# Power.net
KiCad netlist of a schematic drawn in Altium Designer
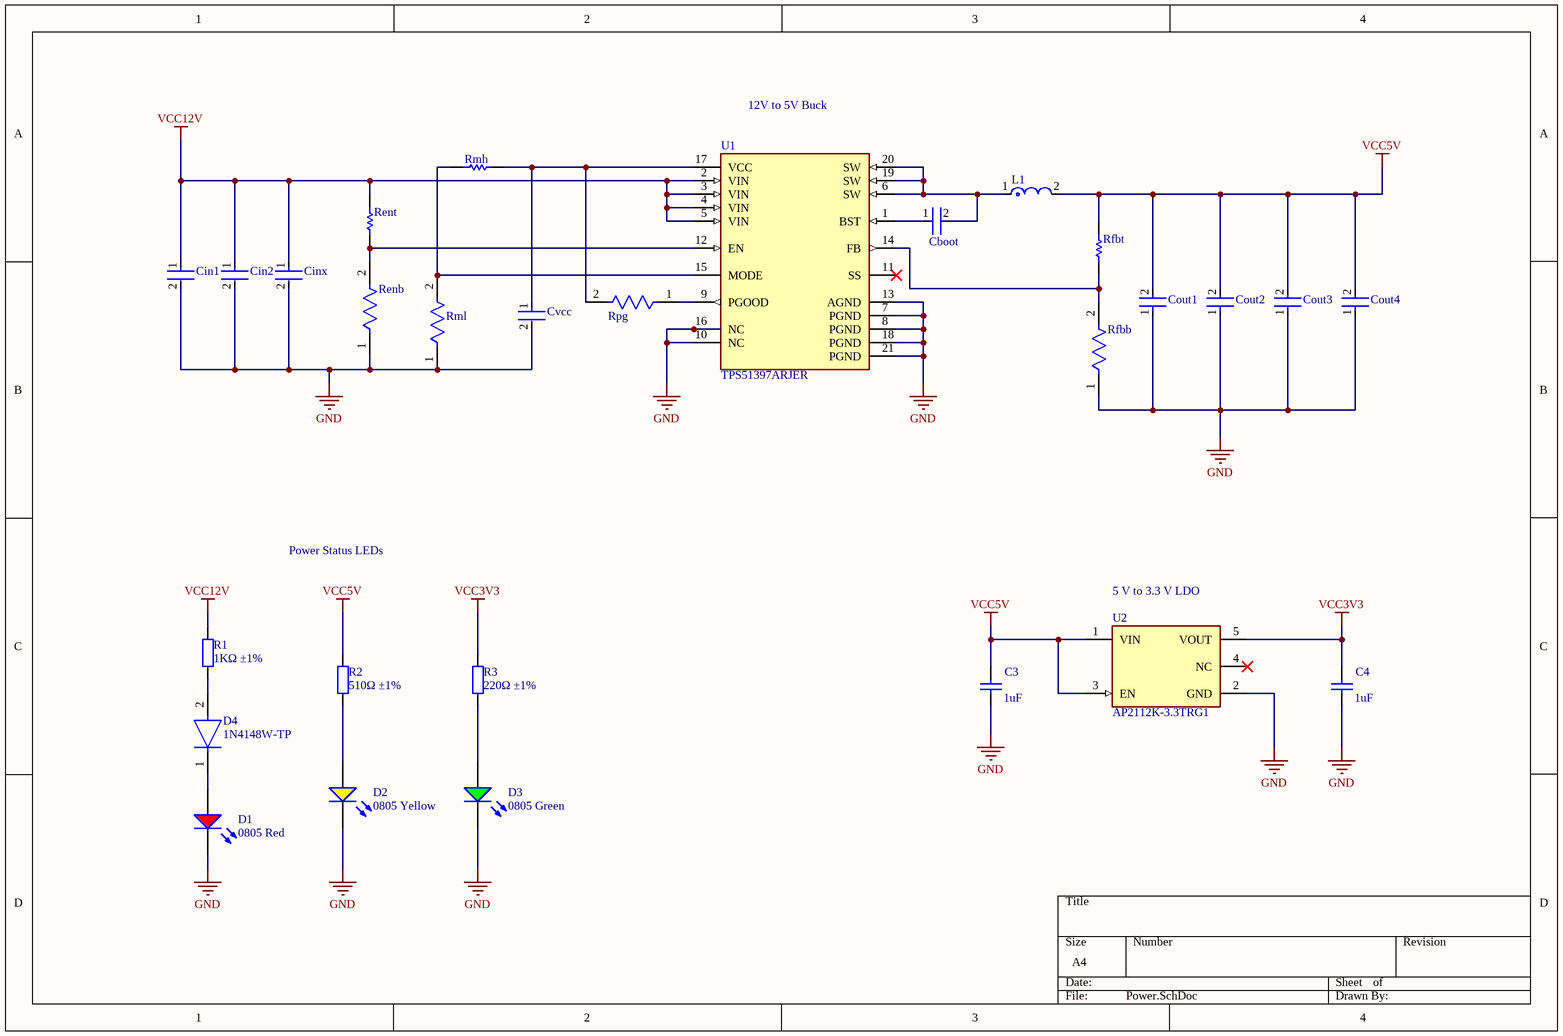
[diagram p0: Power.SchDoc]

(export (version "E")
  (design (tool "Eeschema 10.0.6"))
  (components
    (comp (ref "C3")
      (value "1uF")
      (footprint "0805_C")
      (description "Chip capacitors")
      (fields
        (field (name "MANUFACTURER") "Samsung Electro-Mechanics")
        (field (name "PARTNUMBER") "CL21B105KBFNNNE")
      )
      (libsource (lib "Cap") (part "0805 1uF (105) 10% 50V"))
    )
    (comp (ref "C4")
      (value "1uF")
      (footprint "0805_C")
      (description "Chip capacitors")
      (fields
        (field (name "MANUFACTURER") "Samsung Electro-Mechanics")
        (field (name "PARTNUMBER") "CL21B105KBFNNNE")
      )
      (libsource (lib "Cap") (part "0805 1uF (105) 10% 50V"))
    )
    (comp (ref "Cboot")
      (value "GRM155R71C104KA88D")
      (footprint "FP-GRM15-MFG")
      (description "CAP CER 0.1UF 16V X7R 0402")
      (fields
        (field (name "TOLERANCE") "10%")
        (field (name "OCTOPART") "https://octopart.com/grm155r71c104ka88d-murata-196880")
      )
      (libsource (lib "Altium Content Vault") (part "236180d848d6139a670b325ea6854c9"))
    )
    (comp (ref "Cin1")
      (value "C2012X5R1V226M125AC")
      (footprint "FP-C2012-125-0_2-MFG")
      (description "Multilayer Ceramic Capacitors 22μF ±20% 35V X5R SMD 0805")
      (fields (field (name "TOLERANCE") "20%"))
      (libsource (lib "Altium Content Vault") (part "b4654b650e69147ec39a6b967a45e02"))
    )
    (comp (ref "Cin2")
      (value "C2012X5R1V226M125AC")
      (footprint "FP-C2012-125-0_2-MFG")
      (description "Multilayer Ceramic Capacitors 22μF ±20% 35V X5R SMD 0805")
      (fields (field (name "TOLERANCE") "20%"))
      (libsource (lib "Altium Content Vault") (part "b4654b650e69147ec39a6b967a45e02"))
    )
    (comp (ref "Cinx")
      (value "CGA3E2X7R1H104K080AA")
      (footprint "FP-CGA3E-0_3-0_1-IPC_A")
      (description "Cap Ceramic 100nF 50V X7R 10% Pad SMD 0603 +125°C Automotive T/R")
      (fields (field (name "TOLERANCE") "10%") (field (name "VOLTAGE") "50V"))
      (libsource (lib "Altium Content Vault") (part "b4654b650e69147ec39a6b967a45e02"))
    )
    (comp (ref "Cout1")
      (value "GRM31CR61A476KE15K")
      (footprint "FP-GRM31C-0_2-e0_3_0_8-IPC_A")
      (description "Chip Multilayer Ceramic Capacitors for General Purpose, 1206, 47uF, X5R, 15%, 10%, 10V")
      (fields (field (name "TOLERANCE") "10%"))
      (libsource (lib "Altium Content Vault") (part "02cd4be3c70576c341d710602a673aa"))
    )
    (comp (ref "Cout2")
      (value "GRM31CR61A476KE15K")
      (footprint "FP-GRM31C-0_2-e0_3_0_8-IPC_A")
      (description "Chip Multilayer Ceramic Capacitors for General Purpose, 1206, 47uF, X5R, 15%, 10%, 10V")
      (fields (field (name "TOLERANCE") "10%"))
      (libsource (lib "Altium Content Vault") (part "02cd4be3c70576c341d710602a673aa"))
    )
    (comp (ref "Cout3")
      (value "GRM31CR61A476KE15K")
      (footprint "FP-GRM31C-0_2-e0_3_0_8-IPC_A")
      (description "Chip Multilayer Ceramic Capacitors for General Purpose, 1206, 47uF, X5R, 15%, 10%, 10V")
      (fields (field (name "TOLERANCE") "10%"))
      (libsource (lib "Altium Content Vault") (part "02cd4be3c70576c341d710602a673aa"))
    )
    (comp (ref "Cout4")
      (value "GRM31CR61A476KE15K")
      (footprint "FP-GRM31C-0_2-e0_3_0_8-IPC_A")
      (description "Chip Multilayer Ceramic Capacitors for General Purpose, 1206, 47uF, X5R, 15%, 10%, 10V")
      (fields (field (name "TOLERANCE") "10%"))
      (libsource (lib "Altium Content Vault") (part "02cd4be3c70576c341d710602a673aa"))
    )
    (comp (ref "Cvcc")
      (value "EMK107B7105KA-T")
      (footprint "FP-0603-L_1_6_0_1-W_0_8_0-IPC_C")
      (description "None")
      (fields (field (name "TOLERANCE") "10%"))
      (libsource (lib "Altium Content Vault") (part "02cd4be3c70576c341d710602a673aa"))
    )
    (comp (ref "D1")
      (value "0805 Red")
      (footprint "0805_LED_S1")
      (description "LED")
      (fields
        (field (name "PARTNUMBER") "FC-2012HRK-620D")
        (field (name "MANUFACTURER") "Foshan NationStar Optoelectronics")
      )
      (libsource (lib "LED") (part "0805 LED Red"))
    )
    (comp (ref "D2")
      (value "0805 Yellow")
      (footprint "0805_LED_S1")
      (description "LED")
      (fields (field (name "PARTNUMBER") "17-21SUYC/TR8"))
      (libsource (lib "LED") (part "0805 LED Yellow"))
    )
    (comp (ref "D3")
      (value "0805 Green")
      (footprint "0805_LED_S1")
      (description "LED")
      (libsource (lib "LED") (part "0805 LED Green"))
    )
    (comp (ref "D4")
      (value "1N4148W-TP")
      (footprint "FP-SOD-123-IPC_A")
      (description "DIODE GEN PURP 100V 150MA SOD123")
      (libsource (lib "Altium Content Vault") (part "d7152d700b627762746794eb795d46e"))
    )
    (comp (ref "L1")
      (value "XAL7070-182MEC")
      (footprint "FP-XAL7070-MFG")
      (description "Surface Mount Power Inductor, 1.8 H, 21 A, 25 A, Shielded, 4460 ohm")
      (fields (field (name "TOLERANCE") "20%"))
      (libsource (lib "Altium Content Vault") (part "4cc4b267dca4c8e51f7102f422741d8"))
    )
    (comp (ref "R1")
      (value "1KΩ ±1%")
      (footprint "0603_R")
      (description "Chip resistor")
      (fields (field (name "MANUFACTURER") "Uniroyal Elec") (field (name "PARTNUMBER") "0603WAF1001T5E"))
      (libsource (lib "RES") (part "0603 1K (1001) 1%"))
    )
    (comp (ref "R2")
      (value "510Ω ±1%")
      (footprint "0603_R")
      (description "Chip resistor")
      (fields (field (name "MANUFACTURER") "Uniroyal Elec") (field (name "PARTNUMBER") "0603WAF5100T5E"))
      (libsource (lib "RES") (part "0603 510R (5100) 1%"))
    )
    (comp (ref "R3")
      (value "220Ω ±1%")
      (footprint "0603_R")
      (description "Chip resistor")
      (fields (field (name "MANUFACTURER") "Uniroyal Elec") (field (name "PARTNUMBER") "0603WAF2200T5E"))
      (libsource (lib "RES") (part "0603 220R (2200) 1%"))
    )
    (comp (ref "Renb")
      (value "CRCW040251K1FKED")
      (footprint "FP-CRCW0402-e3-MFG")
      (description "RES Thick Film, 51.1kΩ, 1%, 0.063W, 100ppm/°C, 0402")
      (fields (field (name "TOLERANCE") "1%"))
      (libsource (lib "Altium Content Vault") (part "1029c3af85768c4190bb7ad29bc67b5"))
    )
    (comp (ref "Rent")
      (value "CRCW0402221KFKED")
      (footprint "RESC1005X40X25ML05T05")
      (fields (field (name "MANUFACTURER") "Vishay Dale"))
      (libsource (lib "Altium Content Vault") (part "RES"))
    )
    (comp (ref "Rfbb")
      (value "CRCW040215K0FKED")
      (footprint "FP-CRCW0402-e3-IPC_B")
      (description "RES Thick Film, 15kΩ, 1%, 0.063W, 100ppm/°C, 0402")
      (fields (field (name "TOLERANCE") "1%"))
      (libsource (lib "Altium Content Vault") (part "1029c3af85768c4190bb7ad29bc67b5"))
    )
    (comp (ref "Rfbt")
      (value "CRCW0402110KFKED")
      (footprint "RESC1005X40X25NL05T05")
      (fields (field (name "MANUFACTURER") "Vishay Dale"))
      (libsource (lib "Altium Content Vault") (part "RES"))
    )
    (comp (ref "Rmh")
      (value "330K 1% 0603(1608)")
      (footprint "RESC0603(1608)_M")
      (description "330K 0.1W 1% 0603 (1608 Metric)  SMD")
      (fields (field (name "POWER") "0.1 W") (field (name "TOLERANCE") "1 %"))
      (libsource (lib "Altium Content Vault") (part "RES"))
    )
    (comp (ref "Rml")
      (value "CRCW040215K0FKED")
      (footprint "FP-CRCW0402-e3-IPC_B")
      (description "RES Thick Film, 15kΩ, 1%, 0.063W, 100ppm/°C, 0402")
      (fields (field (name "TOLERANCE") "1%"))
      (libsource (lib "Altium Content Vault") (part "1029c3af85768c4190bb7ad29bc67b5"))
    )
    (comp (ref "Rpg")
      (value "CRCW0402100KFKEDC")
      (footprint "FP-CRCW0402-C-e3-MFG")
      (description "RES 100K OHM 1% 1/16W 0402")
      (fields (field (name "TOLERANCE") "1%"))
      (libsource (lib "Altium Content Vault") (part "1029c3af85768c4190bb7ad29bc67b5"))
    )
    (comp (ref "U1")
      (value "TPS51397ARJER")
      (footprint "FP-RJE0020B-MFG")
      (description "10-A SYNCHRONOUS STEP-DOWN REGUL")
      (libsource (lib "Altium Content Vault") (part "ab47a50a5143bf718f7c4e945efebe0"))
    )
    (comp (ref "U2")
      (value "AP2112K-3.3TRG1")
      (footprint "FP-SOT25-IPC_A")
      (description "IC REG LINEAR 3.3V 600MA SOT25")
      (libsource (lib "Altium Content Vault") (part "c8ab751aee5229183125ab046a11caa"))
    )
  )
  (nets
    (net (code "1") (name "GND") (class "Default")
      (node (ref "C3") (pin "1") (pinfunction "1_1") (pintype "passive"))
      (node (ref "C4") (pin "1") (pinfunction "1_1") (pintype "passive"))
      (node (ref "Cin1") (pin "2") (pinfunction "2_2") (pintype "passive"))
      (node (ref "Cin2") (pin "2") (pinfunction "2_2") (pintype "passive"))
      (node (ref "Cinx") (pin "2") (pinfunction "2_2") (pintype "passive"))
      (node (ref "Cout1") (pin "1") (pinfunction "1_1") (pintype "passive"))
      (node (ref "Cout2") (pin "1") (pinfunction "1_1") (pintype "passive"))
      (node (ref "Cout3") (pin "1") (pinfunction "1_1") (pintype "passive"))
      (node (ref "Cout4") (pin "1") (pinfunction "1_1") (pintype "passive"))
      (node (ref "Cvcc") (pin "2") (pinfunction "2_2") (pintype "passive"))
      (node (ref "D1") (pin "K") (pinfunction "K_K") (pintype "passive"))
      (node (ref "D2") (pin "K") (pinfunction "K_K") (pintype "passive"))
      (node (ref "D3") (pin "K") (pinfunction "K_K") (pintype "passive"))
      (node (ref "Renb") (pin "1") (pinfunction "1_1") (pintype "passive"))
      (node (ref "Rfbb") (pin "1") (pinfunction "1_1") (pintype "passive"))
      (node (ref "Rml") (pin "1") (pinfunction "1_1") (pintype "passive"))
      (node (ref "U1") (pin "10") (pinfunction "NC_10") (pintype "passive"))
      (node (ref "U1") (pin "13") (pinfunction "AGND_13") (pintype "power_in"))
      (node (ref "U1") (pin "16") (pinfunction "NC_16") (pintype "passive"))
      (node (ref "U1") (pin "18") (pinfunction "PGND_18") (pintype "power_in"))
      (node (ref "U1") (pin "21") (pinfunction "PGND_21") (pintype "power_in"))
      (node (ref "U1") (pin "7") (pinfunction "PGND_7") (pintype "power_in"))
      (node (ref "U1") (pin "8") (pinfunction "PGND_8") (pintype "power_in"))
      (node (ref "U2") (pin "2") (pinfunction "GND_2") (pintype "power_in"))
    )
    (net (code "2") (name "Net-(Cboot-Pad2)") (class "Default")
      (node (ref "Cboot") (pin "2") (pinfunction "2_2") (pintype "passive"))
      (node (ref "L1") (pin "1") (pinfunction "1_1") (pintype "passive"))
      (node (ref "U1") (pin "19") (pinfunction "SW_19") (pintype "input"))
      (node (ref "U1") (pin "20") (pinfunction "SW_20") (pintype "input"))
      (node (ref "U1") (pin "6") (pinfunction "SW_6") (pintype "input"))
    )
    (net (code "3") (name "Net-(D2-PadA)") (class "Default")
      (node (ref "D2") (pin "A") (pinfunction "A_A") (pintype "passive"))
      (node (ref "R2") (pin "1") (pinfunction "1_1") (pintype "passive"))
    )
    (net (code "4") (name "Net-(D3-PadA)") (class "Default")
      (node (ref "D3") (pin "A") (pinfunction "A_A") (pintype "passive"))
      (node (ref "R3") (pin "1") (pinfunction "1_1") (pintype "passive"))
    )
    (net (code "5") (name "Net-(D4-A)") (class "Default")
      (node (ref "D4") (pin "2") (pinfunction "A_2") (pintype "passive"))
      (node (ref "R1") (pin "1") (pinfunction "1_1") (pintype "passive"))
    )
    (net (code "6") (name "Net-(D4-C)") (class "Default")
      (node (ref "D1") (pin "A") (pinfunction "A_A") (pintype "passive"))
      (node (ref "D4") (pin "1") (pinfunction "C_1") (pintype "passive"))
    )
    (net (code "7") (name "Net-(U1-BST)") (class "Default")
      (node (ref "Cboot") (pin "1") (pinfunction "1_1") (pintype "passive"))
      (node (ref "U1") (pin "1") (pinfunction "BST_1") (pintype "input"))
    )
    (net (code "8") (name "Net-(U1-EN)") (class "Default")
      (node (ref "Renb") (pin "2") (pinfunction "2_2") (pintype "passive"))
      (node (ref "Rent") (pin "1") (pinfunction "1_1") (pintype "passive"))
      (node (ref "U1") (pin "12") (pinfunction "EN_12") (pintype "input"))
    )
    (net (code "9") (name "Net-(U1-FB)") (class "Default")
      (node (ref "Rfbb") (pin "2") (pinfunction "2_2") (pintype "passive"))
      (node (ref "Rfbt") (pin "1") (pinfunction "1_1") (pintype "passive"))
      (node (ref "U1") (pin "14") (pinfunction "FB_14") (pintype "output"))
    )
    (net (code "10") (name "Net-(U1-MODE)") (class "Default")
      (node (ref "Rmh") (pin "2") (pinfunction "2_2") (pintype "passive"))
      (node (ref "Rml") (pin "2") (pinfunction "2_2") (pintype "passive"))
      (node (ref "U1") (pin "15") (pinfunction "MODE_15") (pintype "passive"))
    )
    (net (code "11") (name "Net-(U1-PGOOD)") (class "Default")
      (node (ref "Rpg") (pin "1") (pinfunction "1_1") (pintype "passive"))
      (node (ref "U1") (pin "9") (pinfunction "PGOOD_9") (pintype "output"))
    )
    (net (code "12") (name "Net-(U1-VCC)") (class "Default")
      (node (ref "Cvcc") (pin "1") (pinfunction "1_1") (pintype "passive"))
      (node (ref "Rmh") (pin "1") (pinfunction "1_1") (pintype "passive"))
      (node (ref "Rpg") (pin "2") (pinfunction "2_2") (pintype "passive"))
      (node (ref "U1") (pin "17") (pinfunction "VCC_17") (pintype "power_in"))
    )
    (net (code "13") (name "VCC3V3") (class "Default")
      (node (ref "C4") (pin "2") (pinfunction "2_2") (pintype "passive"))
      (node (ref "R3") (pin "2") (pinfunction "2_2") (pintype "passive"))
      (node (ref "U2") (pin "5") (pinfunction "VOUT_5") (pintype "power_in"))
    )
    (net (code "14") (name "VCC5V") (class "Default")
      (node (ref "C3") (pin "2") (pinfunction "2_2") (pintype "passive"))
      (node (ref "Cout1") (pin "2") (pinfunction "2_2") (pintype "passive"))
      (node (ref "Cout2") (pin "2") (pinfunction "2_2") (pintype "passive"))
      (node (ref "Cout3") (pin "2") (pinfunction "2_2") (pintype "passive"))
      (node (ref "Cout4") (pin "2") (pinfunction "2_2") (pintype "passive"))
      (node (ref "L1") (pin "2") (pinfunction "2_2") (pintype "passive"))
      (node (ref "R2") (pin "2") (pinfunction "2_2") (pintype "passive"))
      (node (ref "Rfbt") (pin "2") (pinfunction "2_2") (pintype "passive"))
      (node (ref "U2") (pin "1") (pinfunction "VIN_1") (pintype "power_in"))
      (node (ref "U2") (pin "3") (pinfunction "EN_3") (pintype "input"))
    )
    (net (code "15") (name "VCC12V") (class "Default")
      (node (ref "Cin1") (pin "1") (pinfunction "1_1") (pintype "passive"))
      (node (ref "Cin2") (pin "1") (pinfunction "1_1") (pintype "passive"))
      (node (ref "Cinx") (pin "1") (pinfunction "1_1") (pintype "passive"))
      (node (ref "R1") (pin "2") (pinfunction "2_2") (pintype "passive"))
      (node (ref "Rent") (pin "2") (pinfunction "2_2") (pintype "passive"))
      (node (ref "U1") (pin "2") (pinfunction "VIN_2") (pintype "input"))
      (node (ref "U1") (pin "3") (pinfunction "VIN_3") (pintype "input"))
      (node (ref "U1") (pin "4") (pinfunction "VIN_4") (pintype "input"))
      (node (ref "U1") (pin "5") (pinfunction "VIN_5") (pintype "input"))
    )
    (net (code "16") (name "unconnected-(U1-SS-Pad11)") (class "Default")
      (node (ref "U1") (pin "11") (pinfunction "SS_11") (pintype "passive+no_connect"))
    )
    (net (code "17") (name "unconnected-(U2-NC-Pad4)") (class "Default")
      (node (ref "U2") (pin "4") (pinfunction "NC_4") (pintype "passive+no_connect"))
    )
  )
)
